# 07_-_Current_Sense.net
KiCad netlist of a schematic drawn in Altium Designer
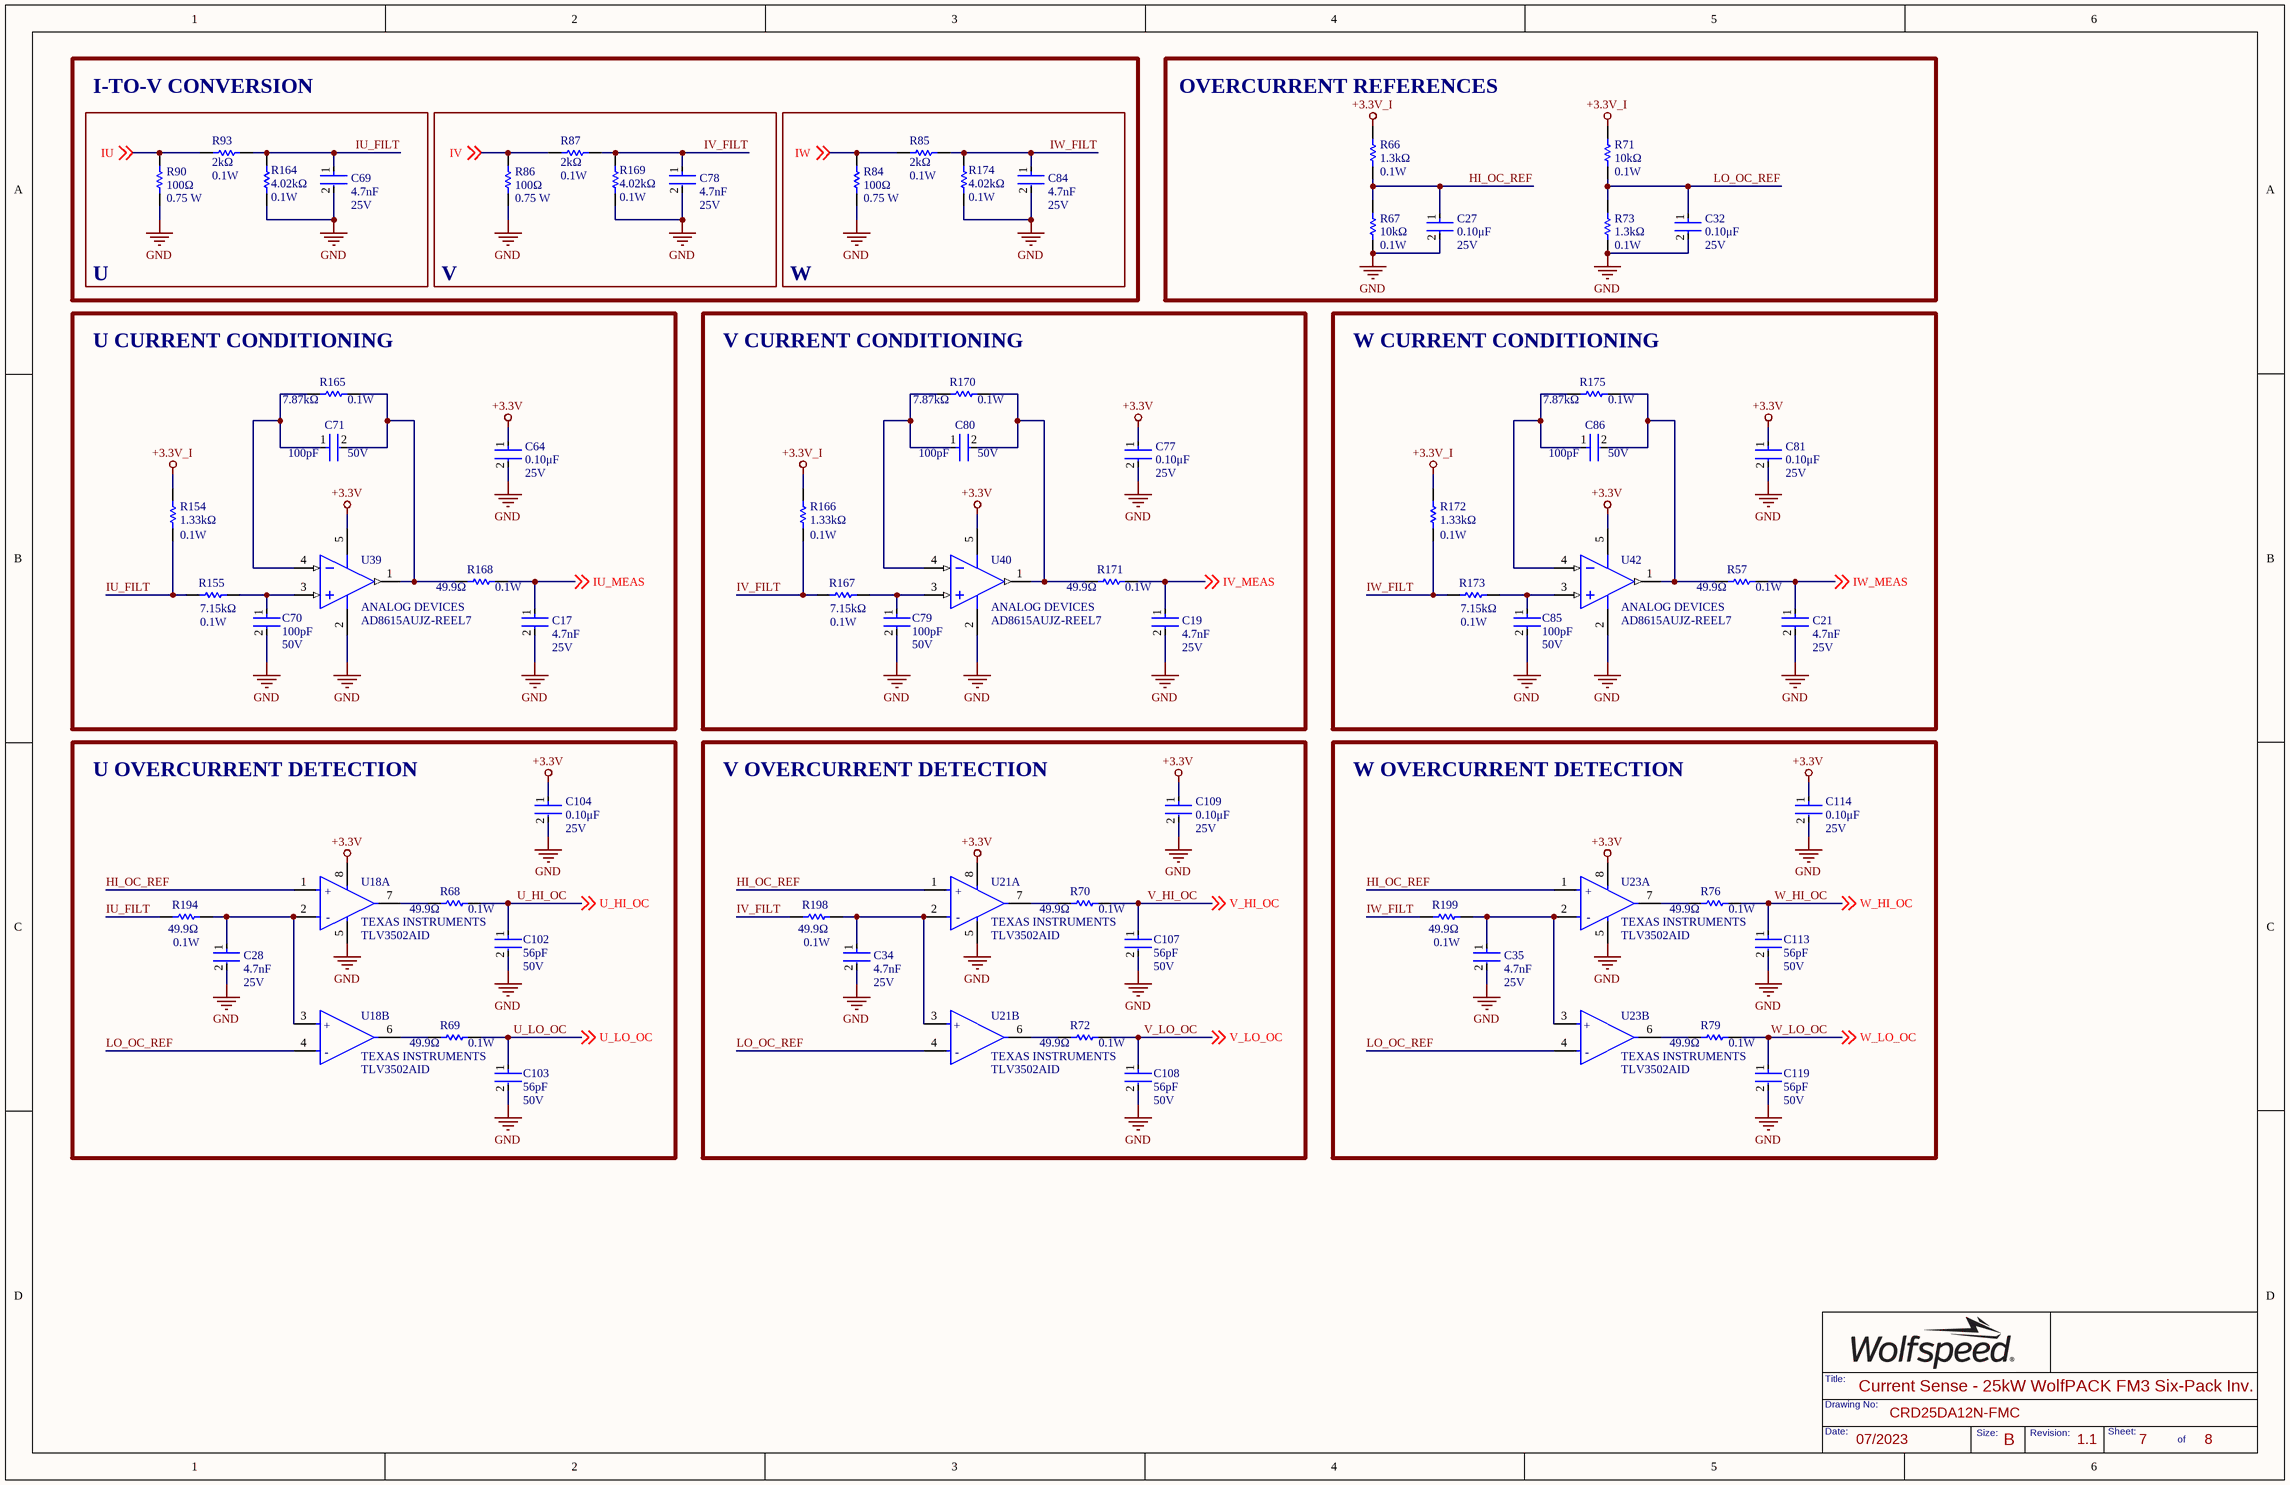
[diagram p0: 07 - Current Sense.SchDoc]

(export (version "E")
  (design (tool "Eeschema 10.0.6"))
  (components
    (comp (ref "C17")
      (value "C0603C472K3RAC7867")
      (footprint "FP-C0603C-CF-IPC_B")
      (description "CAP CER 4700PF 25V 10% X7R 0603")
      (fields
        (field (name "MANUFACTURER") "KEMET")
        (field (name "MANUFACTURER PART NUMBER") "C0603C472K3RACTU")
        (field (name "VOLTAGE RATING") "25V")
        (field (name "CAPACITANCE") "4.7nF")
      )
      (libsource (lib "Inverter_25kW") (part "C0603C472K3RAC7867"))
    )
    (comp (ref "C19")
      (value "C0603C472K3RAC7867")
      (footprint "FP-C0603C-CF-IPC_B")
      (description "CAP CER 4700PF 25V 10% X7R 0603")
      (fields
        (field (name "MANUFACTURER") "KEMET")
        (field (name "MANUFACTURER PART NUMBER") "C0603C472K3RACTU")
        (field (name "VOLTAGE RATING") "25V")
        (field (name "CAPACITANCE") "4.7nF")
      )
      (libsource (lib "Inverter_25kW") (part "C0603C472K3RAC7867"))
    )
    (comp (ref "C21")
      (value "C0603C472K3RAC7867")
      (footprint "FP-C0603C-CF-IPC_B")
      (description "CAP CER 4700PF 25V 10% X7R 0603")
      (fields
        (field (name "MANUFACTURER") "KEMET")
        (field (name "MANUFACTURER PART NUMBER") "C0603C472K3RACTU")
        (field (name "VOLTAGE RATING") "25V")
        (field (name "CAPACITANCE") "4.7nF")
      )
      (libsource (lib "Inverter_25kW") (part "C0603C472K3RAC7867"))
    )
    (comp (ref "C27")
      (value "C0603C104K3RACTU")
      (footprint "FP-C0603C-CF-IPC_B")
      (description "CAP CER 0.1UF 25V X7R 0603")
      (fields
        (field (name "VOLTAGE RATING") "25V")
        (field (name "OCTOPART") "https://octopart.com/c0603c104k3ractu-kemet-127541")
        (field (name "MANUFACTURER") "KEMET")
        (field (name "CAPACITANCE") "0.10μF")
      )
      (libsource (lib "Altium Content Vault") (part "b4654b650e69147ec39a6b967a45e02"))
    )
    (comp (ref "C28")
      (value "C0603C472K3RAC7867")
      (footprint "FP-C0603C-CF-IPC_B")
      (description "CAP CER 4700PF 25V 10% X7R 0603")
      (fields
        (field (name "MANUFACTURER") "KEMET")
        (field (name "MANUFACTURER PART NUMBER") "C0603C472K3RACTU")
        (field (name "VOLTAGE RATING") "25V")
        (field (name "CAPACITANCE") "4.7nF")
      )
      (libsource (lib "Inverter_25kW") (part "C0603C472K3RAC7867"))
    )
    (comp (ref "C32")
      (value "C0603C104K3RACTU")
      (footprint "FP-C0603C-CF-IPC_B")
      (description "CAP CER 0.1UF 25V X7R 0603")
      (fields
        (field (name "VOLTAGE RATING") "25V")
        (field (name "OCTOPART") "https://octopart.com/c0603c104k3ractu-kemet-127541")
        (field (name "MANUFACTURER") "KEMET")
        (field (name "CAPACITANCE") "0.10μF")
      )
      (libsource (lib "Altium Content Vault") (part "b4654b650e69147ec39a6b967a45e02"))
    )
    (comp (ref "C34")
      (value "C0603C472K3RAC7867")
      (footprint "FP-C0603C-CF-IPC_B")
      (description "CAP CER 4700PF 25V 10% X7R 0603")
      (fields
        (field (name "MANUFACTURER") "KEMET")
        (field (name "MANUFACTURER PART NUMBER") "C0603C472K3RACTU")
        (field (name "VOLTAGE RATING") "25V")
        (field (name "CAPACITANCE") "4.7nF")
      )
      (libsource (lib "Inverter_25kW") (part "C0603C472K3RAC7867"))
    )
    (comp (ref "C35")
      (value "C0603C472K3RAC7867")
      (footprint "FP-C0603C-CF-IPC_B")
      (description "CAP CER 4700PF 25V 10% X7R 0603")
      (fields
        (field (name "MANUFACTURER") "KEMET")
        (field (name "MANUFACTURER PART NUMBER") "C0603C472K3RACTU")
        (field (name "VOLTAGE RATING") "25V")
        (field (name "CAPACITANCE") "4.7nF")
      )
      (libsource (lib "Inverter_25kW") (part "C0603C472K3RAC7867"))
    )
    (comp (ref "C64")
      (value "C0603C104K3RACTU")
      (footprint "FP-C0603C-CF-IPC_B")
      (description "CAP CER 0.1UF 25V X7R 0603")
      (fields
        (field (name "VOLTAGE RATING") "25V")
        (field (name "OCTOPART") "https://octopart.com/c0603c104k3ractu-kemet-127541")
        (field (name "MANUFACTURER") "KEMET")
        (field (name "CAPACITANCE") "0.10μF")
      )
      (libsource (lib "Altium Content Vault") (part "b4654b650e69147ec39a6b967a45e02"))
    )
    (comp (ref "C69")
      (value "C0603C472K3RAC7867")
      (footprint "FP-C0603C-CF-IPC_B")
      (description "CAP CER 4700PF 25V 10% X7R 0603")
      (fields
        (field (name "MANUFACTURER") "KEMET")
        (field (name "MANUFACTURER PART NUMBER") "C0603C472K3RACTU")
        (field (name "VOLTAGE RATING") "25V")
        (field (name "CAPACITANCE") "4.7nF")
      )
      (libsource (lib "Inverter_25kW") (part "C0603C472K3RAC7867"))
    )
    (comp (ref "C70")
      (value "CL10C101JB8NNNC")
      (footprint "FP-C0603C-CF-IPC_B")
      (description "CAP CER 100PF 50V C0G/NP0 0603")
      (fields
        (field (name "MANUFACTURER") "SAMSUNG")
        (field (name "TOLERANCE") "5%")
        (field (name "CAPACITANCE") "100pF")
        (field (name "VOLTAGE") "50V")
      )
      (libsource (lib "Inverter_25kW") (part "CL10C101JB8NNNC"))
    )
    (comp (ref "C71")
      (value "CL10C101JB8NNNC")
      (footprint "FP-C0603C-CF-IPC_B")
      (description "CAP CER 100PF 50V C0G/NP0 0603")
      (fields
        (field (name "MANUFACTURER") "SAMSUNG")
        (field (name "TOLERANCE") "5%")
        (field (name "CAPACITANCE") "100pF")
        (field (name "VOLTAGE") "50V")
      )
      (libsource (lib "Inverter_25kW") (part "CL10C101JB8NNNC"))
    )
    (comp (ref "C77")
      (value "C0603C104K3RACTU")
      (footprint "FP-C0603C-CF-IPC_B")
      (description "CAP CER 0.1UF 25V X7R 0603")
      (fields
        (field (name "VOLTAGE RATING") "25V")
        (field (name "OCTOPART") "https://octopart.com/c0603c104k3ractu-kemet-127541")
        (field (name "MANUFACTURER") "KEMET")
        (field (name "CAPACITANCE") "0.10μF")
      )
      (libsource (lib "Altium Content Vault") (part "b4654b650e69147ec39a6b967a45e02"))
    )
    (comp (ref "C78")
      (value "C0603C472K3RAC7867")
      (footprint "FP-C0603C-CF-IPC_B")
      (description "CAP CER 4700PF 25V 10% X7R 0603")
      (fields
        (field (name "MANUFACTURER") "KEMET")
        (field (name "MANUFACTURER PART NUMBER") "C0603C472K3RACTU")
        (field (name "VOLTAGE RATING") "25V")
        (field (name "CAPACITANCE") "4.7nF")
      )
      (libsource (lib "Inverter_25kW") (part "C0603C472K3RAC7867"))
    )
    (comp (ref "C79")
      (value "CL10C101JB8NNNC")
      (footprint "FP-C0603C-CF-IPC_B")
      (description "CAP CER 100PF 50V C0G/NP0 0603")
      (fields
        (field (name "MANUFACTURER") "SAMSUNG")
        (field (name "TOLERANCE") "5%")
        (field (name "CAPACITANCE") "100pF")
        (field (name "VOLTAGE") "50V")
      )
      (libsource (lib "Inverter_25kW") (part "CL10C101JB8NNNC"))
    )
    (comp (ref "C80")
      (value "CL10C101JB8NNNC")
      (footprint "FP-C0603C-CF-IPC_B")
      (description "CAP CER 100PF 50V C0G/NP0 0603")
      (fields
        (field (name "MANUFACTURER") "SAMSUNG")
        (field (name "TOLERANCE") "5%")
        (field (name "CAPACITANCE") "100pF")
        (field (name "VOLTAGE") "50V")
      )
      (libsource (lib "Inverter_25kW") (part "CL10C101JB8NNNC"))
    )
    (comp (ref "C81")
      (value "C0603C104K3RACTU")
      (footprint "FP-C0603C-CF-IPC_B")
      (description "CAP CER 0.1UF 25V X7R 0603")
      (fields
        (field (name "VOLTAGE RATING") "25V")
        (field (name "OCTOPART") "https://octopart.com/c0603c104k3ractu-kemet-127541")
        (field (name "MANUFACTURER") "KEMET")
        (field (name "CAPACITANCE") "0.10μF")
      )
      (libsource (lib "Altium Content Vault") (part "b4654b650e69147ec39a6b967a45e02"))
    )
    (comp (ref "C84")
      (value "C0603C472K3RAC7867")
      (footprint "FP-C0603C-CF-IPC_B")
      (description "CAP CER 4700PF 25V 10% X7R 0603")
      (fields
        (field (name "MANUFACTURER") "KEMET")
        (field (name "MANUFACTURER PART NUMBER") "C0603C472K3RACTU")
        (field (name "VOLTAGE RATING") "25V")
        (field (name "CAPACITANCE") "4.7nF")
      )
      (libsource (lib "Inverter_25kW") (part "C0603C472K3RAC7867"))
    )
    (comp (ref "C85")
      (value "CL10C101JB8NNNC")
      (footprint "FP-C0603C-CF-IPC_B")
      (description "CAP CER 100PF 50V C0G/NP0 0603")
      (fields
        (field (name "MANUFACTURER") "SAMSUNG")
        (field (name "TOLERANCE") "5%")
        (field (name "CAPACITANCE") "100pF")
        (field (name "VOLTAGE") "50V")
      )
      (libsource (lib "Inverter_25kW") (part "CL10C101JB8NNNC"))
    )
    (comp (ref "C86")
      (value "CL10C101JB8NNNC")
      (footprint "FP-C0603C-CF-IPC_B")
      (description "CAP CER 100PF 50V C0G/NP0 0603")
      (fields
        (field (name "MANUFACTURER") "SAMSUNG")
        (field (name "TOLERANCE") "5%")
        (field (name "CAPACITANCE") "100pF")
        (field (name "VOLTAGE") "50V")
      )
      (libsource (lib "Inverter_25kW") (part "CL10C101JB8NNNC"))
    )
    (comp (ref "C102")
      (value "CL10C560JB8NNNC")
      (footprint "FP-C0603C-CF-IPC_B")
      (description "CAP CER 56PF 50V C0G/NP0 0603")
      (fields
        (field (name "MANUFACTURER") "SAMSUNG")
        (field (name "TOLERANCE") "5%")
        (field (name "CAPACITANCE") "56pF")
        (field (name "VOLTAGE RATING") "50V")
      )
      (libsource (lib "Inverter_25kW") (part "CL10C560JB8NNNC"))
    )
    (comp (ref "C103")
      (value "CL10C560JB8NNNC")
      (footprint "FP-C0603C-CF-IPC_B")
      (description "CAP CER 56PF 50V C0G/NP0 0603")
      (fields
        (field (name "MANUFACTURER") "SAMSUNG")
        (field (name "TOLERANCE") "5%")
        (field (name "CAPACITANCE") "56pF")
        (field (name "VOLTAGE RATING") "50V")
      )
      (libsource (lib "Inverter_25kW") (part "CL10C560JB8NNNC"))
    )
    (comp (ref "C104")
      (value "C0603C104K3RACTU")
      (footprint "FP-C0603C-CF-IPC_B")
      (description "CAP CER 0.1UF 25V X7R 0603")
      (fields
        (field (name "VOLTAGE RATING") "25V")
        (field (name "OCTOPART") "https://octopart.com/c0603c104k3ractu-kemet-127541")
        (field (name "MANUFACTURER") "KEMET")
        (field (name "CAPACITANCE") "0.10μF")
      )
      (libsource (lib "Altium Content Vault") (part "b4654b650e69147ec39a6b967a45e02"))
    )
    (comp (ref "C107")
      (value "CL10C560JB8NNNC")
      (footprint "FP-C0603C-CF-IPC_B")
      (description "CAP CER 56PF 50V C0G/NP0 0603")
      (fields
        (field (name "MANUFACTURER") "SAMSUNG")
        (field (name "TOLERANCE") "5%")
        (field (name "CAPACITANCE") "56pF")
        (field (name "VOLTAGE RATING") "50V")
      )
      (libsource (lib "Inverter_25kW") (part "CL10C560JB8NNNC"))
    )
    (comp (ref "C108")
      (value "CL10C560JB8NNNC")
      (footprint "FP-C0603C-CF-IPC_B")
      (description "CAP CER 56PF 50V C0G/NP0 0603")
      (fields
        (field (name "MANUFACTURER") "SAMSUNG")
        (field (name "TOLERANCE") "5%")
        (field (name "CAPACITANCE") "56pF")
        (field (name "VOLTAGE RATING") "50V")
      )
      (libsource (lib "Inverter_25kW") (part "CL10C560JB8NNNC"))
    )
    (comp (ref "C109")
      (value "C0603C104K3RACTU")
      (footprint "FP-C0603C-CF-IPC_B")
      (description "CAP CER 0.1UF 25V X7R 0603")
      (fields
        (field (name "VOLTAGE RATING") "25V")
        (field (name "OCTOPART") "https://octopart.com/c0603c104k3ractu-kemet-127541")
        (field (name "MANUFACTURER") "KEMET")
        (field (name "CAPACITANCE") "0.10μF")
      )
      (libsource (lib "Altium Content Vault") (part "b4654b650e69147ec39a6b967a45e02"))
    )
    (comp (ref "C113")
      (value "CL10C560JB8NNNC")
      (footprint "FP-C0603C-CF-IPC_B")
      (description "CAP CER 56PF 50V C0G/NP0 0603")
      (fields
        (field (name "MANUFACTURER") "SAMSUNG")
        (field (name "TOLERANCE") "5%")
        (field (name "CAPACITANCE") "56pF")
        (field (name "VOLTAGE RATING") "50V")
      )
      (libsource (lib "Inverter_25kW") (part "CL10C560JB8NNNC"))
    )
    (comp (ref "C114")
      (value "C0603C104K3RACTU")
      (footprint "FP-C0603C-CF-IPC_B")
      (description "CAP CER 0.1UF 25V X7R 0603")
      (fields
        (field (name "VOLTAGE RATING") "25V")
        (field (name "OCTOPART") "https://octopart.com/c0603c104k3ractu-kemet-127541")
        (field (name "MANUFACTURER") "KEMET")
        (field (name "CAPACITANCE") "0.10μF")
      )
      (libsource (lib "Altium Content Vault") (part "b4654b650e69147ec39a6b967a45e02"))
    )
    (comp (ref "C119")
      (value "CL10C560JB8NNNC")
      (footprint "FP-C0603C-CF-IPC_B")
      (description "CAP CER 56PF 50V C0G/NP0 0603")
      (fields
        (field (name "MANUFACTURER") "SAMSUNG")
        (field (name "TOLERANCE") "5%")
        (field (name "CAPACITANCE") "56pF")
        (field (name "VOLTAGE RATING") "50V")
      )
      (libsource (lib "Inverter_25kW") (part "CL10C560JB8NNNC"))
    )
    (comp (ref "R57")
      (value "ERJ-3EKF49R9V")
      (footprint "FP-MCR03-IPC_B")
      (description "RES SMD 49.9 OHM 1% 1/10W 0603")
      (fields
        (field (name "MANUFACTURER") "PANASONIC")
        (field (name "TOLERANCE") "1%")
        (field (name "RESISTANCE") "49.9Ω")
        (field (name "POWER RATING") "0.1W")
      )
      (libsource (lib "Inverter_25kW") (part "ERJ-3EKF49R9V"))
    )
    (comp (ref "R66")
      (value "ERA3AEB132V")
      (footprint "FP-MCR03-IPC_B")
      (description "RES SMD 1.3K OHM 0.1% 1/10W 0603")
      (fields
        (field (name "MANUFACTURER") "PANASONIC")
        (field (name "MANUFACTURER PART NUMBER") "ERA-3AEB132V")
        (field (name "POWER RATING") "0.1W")
        (field (name "RESISTANCE") "1.3kΩ")
      )
      (libsource (lib "Inverter_25kW") (part "ERA3AEB132V"))
    )
    (comp (ref "R67")
      (value "ERJ3EKF1002V")
      (footprint "FP-MCR03-IPC_B")
      (description "RES SMD 10K OHM 1% 1/10W 0603")
      (fields
        (field (name "MANUFACTURER") "PANASONIC")
        (field (name "MANUFACTURER PART NUMBER") "ERJ-3EKF1002V")
        (field (name "RESISTANCE") "10kΩ")
        (field (name "MAX POWER DISSIPATION") "0.1W")
      )
      (libsource (lib "Inverter_25kW") (part "ERJ3EKF1002V"))
    )
    (comp (ref "R68")
      (value "ERJ-3EKF49R9V")
      (footprint "FP-MCR03-IPC_B")
      (description "RES SMD 49.9 OHM 1% 1/10W 0603")
      (fields
        (field (name "MANUFACTURER") "PANASONIC")
        (field (name "TOLERANCE") "1%")
        (field (name "RESISTANCE") "49.9Ω")
        (field (name "POWER RATING") "0.1W")
      )
      (libsource (lib "Inverter_25kW") (part "ERJ-3EKF49R9V"))
    )
    (comp (ref "R69")
      (value "ERJ-3EKF49R9V")
      (footprint "FP-MCR03-IPC_B")
      (description "RES SMD 49.9 OHM 1% 1/10W 0603")
      (fields
        (field (name "MANUFACTURER") "PANASONIC")
        (field (name "TOLERANCE") "1%")
        (field (name "RESISTANCE") "49.9Ω")
        (field (name "POWER RATING") "0.1W")
      )
      (libsource (lib "Inverter_25kW") (part "ERJ-3EKF49R9V"))
    )
    (comp (ref "R70")
      (value "ERJ-3EKF49R9V")
      (footprint "FP-MCR03-IPC_B")
      (description "RES SMD 49.9 OHM 1% 1/10W 0603")
      (fields
        (field (name "MANUFACTURER") "PANASONIC")
        (field (name "TOLERANCE") "1%")
        (field (name "RESISTANCE") "49.9Ω")
        (field (name "POWER RATING") "0.1W")
      )
      (libsource (lib "Inverter_25kW") (part "ERJ-3EKF49R9V"))
    )
    (comp (ref "R71")
      (value "ERJ3EKF1002V")
      (footprint "FP-MCR03-IPC_B")
      (description "RES SMD 10K OHM 1% 1/10W 0603")
      (fields
        (field (name "MANUFACTURER") "PANASONIC")
        (field (name "MANUFACTURER PART NUMBER") "ERJ-3EKF1002V")
        (field (name "RESISTANCE") "10kΩ")
        (field (name "MAX POWER DISSIPATION") "0.1W")
      )
      (libsource (lib "Inverter_25kW") (part "ERJ3EKF1002V"))
    )
    (comp (ref "R72")
      (value "ERJ-3EKF49R9V")
      (footprint "FP-MCR03-IPC_B")
      (description "RES SMD 49.9 OHM 1% 1/10W 0603")
      (fields
        (field (name "MANUFACTURER") "PANASONIC")
        (field (name "TOLERANCE") "1%")
        (field (name "RESISTANCE") "49.9Ω")
        (field (name "POWER RATING") "0.1W")
      )
      (libsource (lib "Inverter_25kW") (part "ERJ-3EKF49R9V"))
    )
    (comp (ref "R73")
      (value "ERA3AEB132V")
      (footprint "FP-MCR03-IPC_B")
      (description "RES SMD 1.3K OHM 0.1% 1/10W 0603")
      (fields
        (field (name "MANUFACTURER") "PANASONIC")
        (field (name "MANUFACTURER PART NUMBER") "ERA-3AEB132V")
        (field (name "POWER RATING") "0.1W")
        (field (name "RESISTANCE") "1.3kΩ")
      )
      (libsource (lib "Inverter_25kW") (part "ERA3AEB132V"))
    )
    (comp (ref "R76")
      (value "ERJ-3EKF49R9V")
      (footprint "FP-MCR03-IPC_B")
      (description "RES SMD 49.9 OHM 1% 1/10W 0603")
      (fields
        (field (name "MANUFACTURER") "PANASONIC")
        (field (name "TOLERANCE") "1%")
        (field (name "RESISTANCE") "49.9Ω")
        (field (name "POWER RATING") "0.1W")
      )
      (libsource (lib "Inverter_25kW") (part "ERJ-3EKF49R9V"))
    )
    (comp (ref "R79")
      (value "ERJ-3EKF49R9V")
      (footprint "FP-MCR03-IPC_B")
      (description "RES SMD 49.9 OHM 1% 1/10W 0603")
      (fields
        (field (name "MANUFACTURER") "PANASONIC")
        (field (name "TOLERANCE") "1%")
        (field (name "RESISTANCE") "49.9Ω")
        (field (name "POWER RATING") "0.1W")
      )
      (libsource (lib "Inverter_25kW") (part "ERJ-3EKF49R9V"))
    )
    (comp (ref "R84")
      (value "100Ω")
      (footprint "RESC2010(5025)_N")
      (description "RES 100 OHM 1% 3/4W 2010")
      (fields
        (field (name "TOLERANCE") "1 %")
        (field (name "POWER") "0.75 W")
        (field (name "MANUFACTURER") "YAGEO")
      )
      (libsource (lib "Altium Content Vault") (part "RES"))
    )
    (comp (ref "R85")
      (value "RT0603DRE072KL")
      (footprint "FP-MCR03-IPC_B")
      (description "RES SMD 2K OHM 0.5% 1/10W 0603")
      (fields
        (field (name "MANUFACTURER") "YAGEO")
        (field (name "TOLERANCE") "0.5%")
        (field (name "RESISTANCE") "2kΩ")
        (field (name "POWER RATING") "0.1W")
      )
      (libsource (lib "Inverter_25kW") (part "RT0603DRE072KL"))
    )
    (comp (ref "R86")
      (value "100Ω")
      (footprint "RESC2010(5025)_N")
      (description "RES 100 OHM 1% 3/4W 2010")
      (fields
        (field (name "TOLERANCE") "1 %")
        (field (name "POWER") "0.75 W")
        (field (name "MANUFACTURER") "YAGEO")
      )
      (libsource (lib "Altium Content Vault") (part "RES"))
    )
    (comp (ref "R87")
      (value "RT0603DRE072KL")
      (footprint "FP-MCR03-IPC_B")
      (description "RES SMD 2K OHM 0.5% 1/10W 0603")
      (fields
        (field (name "MANUFACTURER") "YAGEO")
        (field (name "TOLERANCE") "0.5%")
        (field (name "RESISTANCE") "2kΩ")
        (field (name "POWER RATING") "0.1W")
      )
      (libsource (lib "Inverter_25kW") (part "RT0603DRE072KL"))
    )
    (comp (ref "R90")
      (value "100Ω")
      (footprint "RESC2010(5025)_N")
      (description "RES 100 OHM 1% 3/4W 2010")
      (fields
        (field (name "TOLERANCE") "1 %")
        (field (name "POWER") "0.75 W")
        (field (name "MANUFACTURER") "YAGEO")
      )
      (libsource (lib "Altium Content Vault") (part "RES"))
    )
    (comp (ref "R93")
      (value "RT0603DRE072KL")
      (footprint "FP-MCR03-IPC_B")
      (description "RES SMD 2K OHM 0.5% 1/10W 0603")
      (fields
        (field (name "MANUFACTURER") "YAGEO")
        (field (name "TOLERANCE") "0.5%")
        (field (name "RESISTANCE") "2kΩ")
        (field (name "POWER RATING") "0.1W")
      )
      (libsource (lib "Inverter_25kW") (part "RT0603DRE072KL"))
    )
    (comp (ref "R154")
      (value "RMCF0603FT1K33")
      (footprint "FP-MCR03-IPC_B")
      (description "RES 1.33K OHM 1% 1/10W 0603")
      (fields
        (field (name "MANUFACTURER") "STACKPOLE")
        (field (name "TOLERANCE") "1%")
        (field (name "POWER RATING") "0.1W")
        (field (name "RESISTANCE") "1.33kΩ")
      )
      (libsource (lib "Inverter_25kW") (part "RMCF0603FT1K33"))
    )
    (comp (ref "R155")
      (value "RMCF0603FT7K15")
      (footprint "FP-MCR03-IPC_B")
      (description "RES 7.15K OHM 1% 1/10W 0603")
      (fields
        (field (name "MANUFACTURER") "STACKPOLE")
        (field (name "TOLERANCE") "1%")
        (field (name "RESISTANCE") "7.15kΩ")
        (field (name "POWER RATING") "0.1W")
      )
      (libsource (lib "Inverter_25kW") (part "RMCF0603FT7K15"))
    )
    (comp (ref "R164")
      (value "ERA3AEB4021V")
      (footprint "FP-MCR03-IPC_B")
      (description "RES SMD 4.02KOHM 0.1% 1/10W 0603")
      (fields
        (field (name "MANUFACTURER") "PANASONIC")
        (field (name "MANUFACTURER PART NUMBER") "ERA-3AEB4021V")
        (field (name "RESISTANCE") "4.02kΩ")
        (field (name "POWER RATING") "0.1W")
      )
      (libsource (lib "Inverter_25kW") (part "ERA3AEB4021V"))
    )
    (comp (ref "R165")
      (value "RC0603FR-077K87L")
      (footprint "FP-MCR03-IPC_B")
      (description "RES 7.87K OHM 1% 1/10W 0603")
      (fields
        (field (name "MANUFACTURER") "YAGEO")
        (field (name "TOLERANCE") "1%")
        (field (name "RESISTANCE") "7.87kΩ")
        (field (name "MAX POWER DISSIPATION") "0.1W")
      )
      (libsource (lib "Inverter_25kW") (part "RC0603FR-077K87L"))
    )
    (comp (ref "R166")
      (value "RMCF0603FT1K33")
      (footprint "FP-MCR03-IPC_B")
      (description "RES 1.33K OHM 1% 1/10W 0603")
      (fields
        (field (name "MANUFACTURER") "STACKPOLE")
        (field (name "TOLERANCE") "1%")
        (field (name "POWER RATING") "0.1W")
        (field (name "RESISTANCE") "1.33kΩ")
      )
      (libsource (lib "Inverter_25kW") (part "RMCF0603FT1K33"))
    )
    (comp (ref "R167")
      (value "RMCF0603FT7K15")
      (footprint "FP-MCR03-IPC_B")
      (description "RES 7.15K OHM 1% 1/10W 0603")
      (fields
        (field (name "MANUFACTURER") "STACKPOLE")
        (field (name "TOLERANCE") "1%")
        (field (name "RESISTANCE") "7.15kΩ")
        (field (name "POWER RATING") "0.1W")
      )
      (libsource (lib "Inverter_25kW") (part "RMCF0603FT7K15"))
    )
    (comp (ref "R168")
      (value "ERJ-3EKF49R9V")
      (footprint "FP-MCR03-IPC_B")
      (description "RES SMD 49.9 OHM 1% 1/10W 0603")
      (fields
        (field (name "MANUFACTURER") "PANASONIC")
        (field (name "TOLERANCE") "1%")
        (field (name "RESISTANCE") "49.9Ω")
        (field (name "POWER RATING") "0.1W")
      )
      (libsource (lib "Inverter_25kW") (part "ERJ-3EKF49R9V"))
    )
    (comp (ref "R169")
      (value "ERA3AEB4021V")
      (footprint "FP-MCR03-IPC_B")
      (description "RES SMD 4.02KOHM 0.1% 1/10W 0603")
      (fields
        (field (name "MANUFACTURER") "PANASONIC")
        (field (name "MANUFACTURER PART NUMBER") "ERA-3AEB4021V")
        (field (name "RESISTANCE") "4.02kΩ")
        (field (name "POWER RATING") "0.1W")
      )
      (libsource (lib "Inverter_25kW") (part "ERA3AEB4021V"))
    )
    (comp (ref "R170")
      (value "RC0603FR-077K87L")
      (footprint "FP-MCR03-IPC_B")
      (description "RES 7.87K OHM 1% 1/10W 0603")
      (fields
        (field (name "MANUFACTURER") "YAGEO")
        (field (name "TOLERANCE") "1%")
        (field (name "RESISTANCE") "7.87kΩ")
        (field (name "MAX POWER DISSIPATION") "0.1W")
      )
      (libsource (lib "Inverter_25kW") (part "RC0603FR-077K87L"))
    )
    (comp (ref "R171")
      (value "ERJ-3EKF49R9V")
      (footprint "FP-MCR03-IPC_B")
      (description "RES SMD 49.9 OHM 1% 1/10W 0603")
      (fields
        (field (name "MANUFACTURER") "PANASONIC")
        (field (name "TOLERANCE") "1%")
        (field (name "RESISTANCE") "49.9Ω")
        (field (name "POWER RATING") "0.1W")
      )
      (libsource (lib "Inverter_25kW") (part "ERJ-3EKF49R9V"))
    )
    (comp (ref "R172")
      (value "RMCF0603FT1K33")
      (footprint "FP-MCR03-IPC_B")
      (description "RES 1.33K OHM 1% 1/10W 0603")
      (fields
        (field (name "MANUFACTURER") "STACKPOLE")
        (field (name "TOLERANCE") "1%")
        (field (name "POWER RATING") "0.1W")
        (field (name "RESISTANCE") "1.33kΩ")
      )
      (libsource (lib "Inverter_25kW") (part "RMCF0603FT1K33"))
    )
    (comp (ref "R173")
      (value "RMCF0603FT7K15")
      (footprint "FP-MCR03-IPC_B")
      (description "RES 7.15K OHM 1% 1/10W 0603")
      (fields
        (field (name "MANUFACTURER") "STACKPOLE")
        (field (name "TOLERANCE") "1%")
        (field (name "RESISTANCE") "7.15kΩ")
        (field (name "POWER RATING") "0.1W")
      )
      (libsource (lib "Inverter_25kW") (part "RMCF0603FT7K15"))
    )
    (comp (ref "R174")
      (value "ERA3AEB4021V")
      (footprint "FP-MCR03-IPC_B")
      (description "RES SMD 4.02KOHM 0.1% 1/10W 0603")
      (fields
        (field (name "MANUFACTURER") "PANASONIC")
        (field (name "MANUFACTURER PART NUMBER") "ERA-3AEB4021V")
        (field (name "RESISTANCE") "4.02kΩ")
        (field (name "POWER RATING") "0.1W")
      )
      (libsource (lib "Inverter_25kW") (part "ERA3AEB4021V"))
    )
    (comp (ref "R175")
      (value "RC0603FR-077K87L")
      (footprint "FP-MCR03-IPC_B")
      (description "RES 7.87K OHM 1% 1/10W 0603")
      (fields
        (field (name "MANUFACTURER") "YAGEO")
        (field (name "TOLERANCE") "1%")
        (field (name "RESISTANCE") "7.87kΩ")
        (field (name "MAX POWER DISSIPATION") "0.1W")
      )
      (libsource (lib "Inverter_25kW") (part "RC0603FR-077K87L"))
    )
    (comp (ref "R194")
      (value "ERJ-3EKF49R9V")
      (footprint "FP-MCR03-IPC_B")
      (description "RES SMD 49.9 OHM 1% 1/10W 0603")
      (fields
        (field (name "MANUFACTURER") "PANASONIC")
        (field (name "TOLERANCE") "1%")
        (field (name "RESISTANCE") "49.9Ω")
        (field (name "POWER RATING") "0.1W")
      )
      (libsource (lib "Inverter_25kW") (part "ERJ-3EKF49R9V"))
    )
    (comp (ref "R198")
      (value "ERJ-3EKF49R9V")
      (footprint "FP-MCR03-IPC_B")
      (description "RES SMD 49.9 OHM 1% 1/10W 0603")
      (fields
        (field (name "MANUFACTURER") "PANASONIC")
        (field (name "TOLERANCE") "1%")
        (field (name "RESISTANCE") "49.9Ω")
        (field (name "POWER RATING") "0.1W")
      )
      (libsource (lib "Inverter_25kW") (part "ERJ-3EKF49R9V"))
    )
    (comp (ref "R199")
      (value "ERJ-3EKF49R9V")
      (footprint "FP-MCR03-IPC_B")
      (description "RES SMD 49.9 OHM 1% 1/10W 0603")
      (fields
        (field (name "MANUFACTURER") "PANASONIC")
        (field (name "TOLERANCE") "1%")
        (field (name "RESISTANCE") "49.9Ω")
        (field (name "POWER RATING") "0.1W")
      )
      (libsource (lib "Inverter_25kW") (part "ERJ-3EKF49R9V"))
    )
    (comp (ref "U18")
      (value "TLV3502AID")
      (footprint "FP-D0008A-IPC_B")
      (description "IC COMPARATOR R-R HI-SPD 8-SOIC")
      (fields
        (field (name "OCTOPART") "https://octopart.com/tlv3502aid-texas+instruments-428400")
        (field (name "MANUFACTURER") "TEXAS INSTRUMENTS")
        (field (name "MANUFACTURER PRINT") "TEXAS INSTRUMENTS")
      )
      (libsource (lib "Inverter_25kW") (part "CMP-04896-000023-1"))
    )
    (comp (ref "U21")
      (value "TLV3502AID")
      (footprint "FP-D0008A-IPC_B")
      (description "IC COMPARATOR R-R HI-SPD 8-SOIC")
      (fields
        (field (name "OCTOPART") "https://octopart.com/tlv3502aid-texas+instruments-428400")
        (field (name "MANUFACTURER") "TEXAS INSTRUMENTS")
        (field (name "MANUFACTURER PRINT") "TEXAS INSTRUMENTS")
      )
      (libsource (lib "Inverter_25kW") (part "CMP-04896-000023-1"))
    )
    (comp (ref "U23")
      (value "TLV3502AID")
      (footprint "FP-D0008A-IPC_B")
      (description "IC COMPARATOR R-R HI-SPD 8-SOIC")
      (fields
        (field (name "OCTOPART") "https://octopart.com/tlv3502aid-texas+instruments-428400")
        (field (name "MANUFACTURER") "TEXAS INSTRUMENTS")
        (field (name "MANUFACTURER PRINT") "TEXAS INSTRUMENTS")
      )
      (libsource (lib "Inverter_25kW") (part "CMP-04896-000023-1"))
    )
    (comp (ref "U39")
      (value "AD8615AUJZ-REEL7")
      (footprint "ADI-UJ-5_M")
      (description "IC OPAMP GP 1 CIRCUIT TSOT23-5")
      (fields
        (field (name "MANUFACTURER") "ANALOG DEVICES")
        (field (name "GENERIC PART NUMBER") "AD8615")
        (field (name "MANUFACTURER PART NUMBER") "AD8615AUJZ-REEL7")
      )
      (libsource (lib "Altium Content Vault") (part "ADI-ADxxxx-X-5"))
    )
    (comp (ref "U40")
      (value "AD8615AUJZ-REEL7")
      (footprint "ADI-UJ-5_M")
      (description "IC OPAMP GP 1 CIRCUIT TSOT23-5")
      (fields
        (field (name "MANUFACTURER") "ANALOG DEVICES")
        (field (name "GENERIC PART NUMBER") "AD8615")
        (field (name "MANUFACTURER PART NUMBER") "AD8615AUJZ-REEL7")
      )
      (libsource (lib "Altium Content Vault") (part "ADI-ADxxxx-X-5"))
    )
    (comp (ref "U42")
      (value "AD8615AUJZ-REEL7")
      (footprint "ADI-UJ-5_M")
      (description "IC OPAMP GP 1 CIRCUIT TSOT23-5")
      (fields
        (field (name "MANUFACTURER") "ANALOG DEVICES")
        (field (name "GENERIC PART NUMBER") "AD8615")
        (field (name "MANUFACTURER PART NUMBER") "AD8615AUJZ-REEL7")
      )
      (libsource (lib "Altium Content Vault") (part "ADI-ADxxxx-X-5"))
    )
  )
  (nets
    (net (code "1") (name "+3.3V") (class "Default")
      (node (ref "C104") (pin "1") (pinfunction "1_1") (pintype "passive"))
      (node (ref "C109") (pin "1") (pinfunction "1_1") (pintype "passive"))
      (node (ref "C114") (pin "1") (pinfunction "1_1") (pintype "passive"))
      (node (ref "C64") (pin "1") (pinfunction "1_1") (pintype "passive"))
      (node (ref "C77") (pin "1") (pinfunction "1_1") (pintype "passive"))
      (node (ref "C81") (pin "1") (pinfunction "1_1") (pintype "passive"))
      (node (ref "U18") (pin "8") (pinfunction "V+_8") (pintype "power_in"))
      (node (ref "U21") (pin "8") (pinfunction "V+_8") (pintype "power_in"))
      (node (ref "U23") (pin "8") (pinfunction "V+_8") (pintype "power_in"))
      (node (ref "U39") (pin "5") (pinfunction "+V_5") (pintype "power_in"))
      (node (ref "U40") (pin "5") (pinfunction "+V_5") (pintype "power_in"))
      (node (ref "U42") (pin "5") (pinfunction "+V_5") (pintype "power_in"))
    )
    (net (code "2") (name "+3.3V_I") (class "Default")
      (node (ref "R154") (pin "2") (pinfunction "2_2") (pintype "passive"))
      (node (ref "R166") (pin "2") (pinfunction "2_2") (pintype "passive"))
      (node (ref "R172") (pin "2") (pinfunction "2_2") (pintype "passive"))
      (node (ref "R66") (pin "2") (pinfunction "2_2") (pintype "passive"))
      (node (ref "R71") (pin "2") (pinfunction "2_2") (pintype "passive"))
    )
    (net (code "3") (name "/HI_OC_REF") (class "Default")
      (node (ref "C27") (pin "1") (pinfunction "1_1") (pintype "passive"))
      (node (ref "R66") (pin "1") (pinfunction "1_1") (pintype "passive"))
      (node (ref "R67") (pin "2") (pinfunction "2_2") (pintype "passive"))
      (node (ref "U18") (pin "1") (pinfunction "+IN_A_1") (pintype "tri_state"))
      (node (ref "U21") (pin "1") (pinfunction "+IN_A_1") (pintype "tri_state"))
      (node (ref "U23") (pin "1") (pinfunction "+IN_A_1") (pintype "tri_state"))
    )
    (net (code "4") (name "/IU_FILT") (class "Default")
      (node (ref "C69") (pin "1") (pinfunction "1_1") (pintype "passive"))
      (node (ref "R154") (pin "1") (pinfunction "1_1") (pintype "passive"))
      (node (ref "R155") (pin "1") (pinfunction "1_1") (pintype "passive"))
      (node (ref "R164") (pin "2") (pinfunction "2_2") (pintype "passive"))
      (node (ref "R194") (pin "1") (pinfunction "1_1") (pintype "passive"))
      (node (ref "R93") (pin "2") (pinfunction "2_2") (pintype "passive"))
    )
    (net (code "5") (name "/IV_FILT") (class "Default")
      (node (ref "C78") (pin "1") (pinfunction "1_1") (pintype "passive"))
      (node (ref "R166") (pin "1") (pinfunction "1_1") (pintype "passive"))
      (node (ref "R167") (pin "1") (pinfunction "1_1") (pintype "passive"))
      (node (ref "R169") (pin "2") (pinfunction "2_2") (pintype "passive"))
      (node (ref "R198") (pin "1") (pinfunction "1_1") (pintype "passive"))
      (node (ref "R87") (pin "2") (pinfunction "2_2") (pintype "passive"))
    )
    (net (code "6") (name "/IW_FILT") (class "Default")
      (node (ref "C84") (pin "1") (pinfunction "1_1") (pintype "passive"))
      (node (ref "R172") (pin "1") (pinfunction "1_1") (pintype "passive"))
      (node (ref "R173") (pin "1") (pinfunction "1_1") (pintype "passive"))
      (node (ref "R174") (pin "2") (pinfunction "2_2") (pintype "passive"))
      (node (ref "R199") (pin "1") (pinfunction "1_1") (pintype "passive"))
      (node (ref "R85") (pin "2") (pinfunction "2_2") (pintype "passive"))
    )
    (net (code "7") (name "/LO_OC_REF") (class "Default")
      (node (ref "C32") (pin "1") (pinfunction "1_1") (pintype "passive"))
      (node (ref "R71") (pin "1") (pinfunction "1_1") (pintype "passive"))
      (node (ref "R73") (pin "2") (pinfunction "2_2") (pintype "passive"))
      (node (ref "U18") (pin "4") (pinfunction "-IN_B_4") (pintype "tri_state"))
      (node (ref "U21") (pin "4") (pinfunction "-IN_B_4") (pintype "tri_state"))
      (node (ref "U23") (pin "4") (pinfunction "-IN_B_4") (pintype "tri_state"))
    )
    (net (code "8") (name "GND") (class "Default")
      (node (ref "C102") (pin "2") (pinfunction "2_2") (pintype "passive"))
      (node (ref "C103") (pin "2") (pinfunction "2_2") (pintype "passive"))
      (node (ref "C104") (pin "2") (pinfunction "2_2") (pintype "passive"))
      (node (ref "C107") (pin "2") (pinfunction "2_2") (pintype "passive"))
      (node (ref "C108") (pin "2") (pinfunction "2_2") (pintype "passive"))
      (node (ref "C109") (pin "2") (pinfunction "2_2") (pintype "passive"))
      (node (ref "C113") (pin "2") (pinfunction "2_2") (pintype "passive"))
      (node (ref "C114") (pin "2") (pinfunction "2_2") (pintype "passive"))
      (node (ref "C119") (pin "2") (pinfunction "2_2") (pintype "passive"))
      (node (ref "C17") (pin "2") (pinfunction "2_2") (pintype "passive"))
      (node (ref "C19") (pin "2") (pinfunction "2_2") (pintype "passive"))
      (node (ref "C21") (pin "2") (pinfunction "2_2") (pintype "passive"))
      (node (ref "C27") (pin "2") (pinfunction "2_2") (pintype "passive"))
      (node (ref "C28") (pin "2") (pinfunction "2_2") (pintype "passive"))
      (node (ref "C32") (pin "2") (pinfunction "2_2") (pintype "passive"))
      (node (ref "C34") (pin "2") (pinfunction "2_2") (pintype "passive"))
      (node (ref "C35") (pin "2") (pinfunction "2_2") (pintype "passive"))
      (node (ref "C64") (pin "2") (pinfunction "2_2") (pintype "passive"))
      (node (ref "C69") (pin "2") (pinfunction "2_2") (pintype "passive"))
      (node (ref "C70") (pin "2") (pinfunction "2_2") (pintype "passive"))
      (node (ref "C77") (pin "2") (pinfunction "2_2") (pintype "passive"))
      (node (ref "C78") (pin "2") (pinfunction "2_2") (pintype "passive"))
      (node (ref "C79") (pin "2") (pinfunction "2_2") (pintype "passive"))
      (node (ref "C81") (pin "2") (pinfunction "2_2") (pintype "passive"))
      (node (ref "C84") (pin "2") (pinfunction "2_2") (pintype "passive"))
      (node (ref "C85") (pin "2") (pinfunction "2_2") (pintype "passive"))
      (node (ref "R164") (pin "1") (pinfunction "1_1") (pintype "passive"))
      (node (ref "R169") (pin "1") (pinfunction "1_1") (pintype "passive"))
      (node (ref "R174") (pin "1") (pinfunction "1_1") (pintype "passive"))
      (node (ref "R67") (pin "1") (pinfunction "1_1") (pintype "passive"))
      (node (ref "R73") (pin "1") (pinfunction "1_1") (pintype "passive"))
      (node (ref "R84") (pin "1") (pinfunction "1_1") (pintype "passive"))
      (node (ref "R86") (pin "1") (pinfunction "1_1") (pintype "passive"))
      (node (ref "R90") (pin "1") (pinfunction "1_1") (pintype "passive"))
      (node (ref "U18") (pin "5") (pinfunction "V-_5") (pintype "power_in"))
      (node (ref "U21") (pin "5") (pinfunction "V-_5") (pintype "power_in"))
      (node (ref "U23") (pin "5") (pinfunction "V-_5") (pintype "power_in"))
      (node (ref "U39") (pin "2") (pinfunction "-V_2") (pintype "power_in"))
      (node (ref "U40") (pin "2") (pinfunction "-V_2") (pintype "power_in"))
      (node (ref "U42") (pin "2") (pinfunction "-V_2") (pintype "power_in"))
    )
    (net (code "9") (name "IU") (class "Default")
      (node (ref "R90") (pin "2") (pinfunction "2_2") (pintype "passive"))
      (node (ref "R93") (pin "1") (pinfunction "1_1") (pintype "passive"))
    )
    (net (code "10") (name "IU_MEAS") (class "Default")
      (node (ref "C17") (pin "1") (pinfunction "1_1") (pintype "passive"))
      (node (ref "R168") (pin "2") (pinfunction "2_2") (pintype "passive"))
    )
    (net (code "11") (name "IV") (class "Default")
      (node (ref "R86") (pin "2") (pinfunction "2_2") (pintype "passive"))
      (node (ref "R87") (pin "1") (pinfunction "1_1") (pintype "passive"))
    )
    (net (code "12") (name "IV_MEAS") (class "Default")
      (node (ref "C19") (pin "1") (pinfunction "1_1") (pintype "passive"))
      (node (ref "R171") (pin "2") (pinfunction "2_2") (pintype "passive"))
    )
    (net (code "13") (name "IW") (class "Default")
      (node (ref "R84") (pin "2") (pinfunction "2_2") (pintype "passive"))
      (node (ref "R85") (pin "1") (pinfunction "1_1") (pintype "passive"))
    )
    (net (code "14") (name "IW_MEAS") (class "Default")
      (node (ref "C21") (pin "1") (pinfunction "1_1") (pintype "passive"))
      (node (ref "R57") (pin "2") (pinfunction "2_2") (pintype "passive"))
    )
    (net (code "15") (name "Net-(U18A--IN_A)") (class "Default")
      (node (ref "C28") (pin "1") (pinfunction "1_1") (pintype "passive"))
      (node (ref "R194") (pin "2") (pinfunction "2_2") (pintype "passive"))
      (node (ref "U18") (pin "2") (pinfunction "-IN_A_2") (pintype "tri_state"))
      (node (ref "U18") (pin "3") (pinfunction "+IN_B_3") (pintype "tri_state"))
    )
    (net (code "16") (name "Net-(U18A-OUT_A)") (class "Default")
      (node (ref "R68") (pin "1") (pinfunction "1_1") (pintype "passive"))
      (node (ref "U18") (pin "7") (pinfunction "OUT_A_7") (pintype "passive"))
    )
    (net (code "17") (name "Net-(U18B-OUT_B)") (class "Default")
      (node (ref "R69") (pin "1") (pinfunction "1_1") (pintype "passive"))
      (node (ref "U18") (pin "6") (pinfunction "OUT_B_6") (pintype "passive"))
    )
    (net (code "18") (name "Net-(U21A--IN_A)") (class "Default")
      (node (ref "C34") (pin "1") (pinfunction "1_1") (pintype "passive"))
      (node (ref "R198") (pin "2") (pinfunction "2_2") (pintype "passive"))
      (node (ref "U21") (pin "2") (pinfunction "-IN_A_2") (pintype "tri_state"))
      (node (ref "U21") (pin "3") (pinfunction "+IN_B_3") (pintype "tri_state"))
    )
    (net (code "19") (name "Net-(U21A-OUT_A)") (class "Default")
      (node (ref "R70") (pin "1") (pinfunction "1_1") (pintype "passive"))
      (node (ref "U21") (pin "7") (pinfunction "OUT_A_7") (pintype "passive"))
    )
    (net (code "20") (name "Net-(U21B-OUT_B)") (class "Default")
      (node (ref "R72") (pin "1") (pinfunction "1_1") (pintype "passive"))
      (node (ref "U21") (pin "6") (pinfunction "OUT_B_6") (pintype "passive"))
    )
    (net (code "21") (name "Net-(U23A--IN_A)") (class "Default")
      (node (ref "C35") (pin "1") (pinfunction "1_1") (pintype "passive"))
      (node (ref "R199") (pin "2") (pinfunction "2_2") (pintype "passive"))
      (node (ref "U23") (pin "2") (pinfunction "-IN_A_2") (pintype "tri_state"))
      (node (ref "U23") (pin "3") (pinfunction "+IN_B_3") (pintype "tri_state"))
    )
    (net (code "22") (name "Net-(U23A-OUT_A)") (class "Default")
      (node (ref "R76") (pin "1") (pinfunction "1_1") (pintype "passive"))
      (node (ref "U23") (pin "7") (pinfunction "OUT_A_7") (pintype "passive"))
    )
    (net (code "23") (name "Net-(U23B-OUT_B)") (class "Default")
      (node (ref "R79") (pin "1") (pinfunction "1_1") (pintype "passive"))
      (node (ref "U23") (pin "6") (pinfunction "OUT_B_6") (pintype "passive"))
    )
    (net (code "24") (name "Net-(U39-+IN)") (class "Default")
      (node (ref "C70") (pin "1") (pinfunction "1_1") (pintype "passive"))
      (node (ref "R155") (pin "2") (pinfunction "2_2") (pintype "passive"))
      (node (ref "U39") (pin "3") (pinfunction "+IN_3") (pintype "input"))
    )
    (net (code "25") (name "Net-(U39--IN)") (class "Default")
      (node (ref "C71") (pin "1") (pinfunction "1_1") (pintype "passive"))
      (node (ref "R165") (pin "1") (pinfunction "1_1") (pintype "passive"))
      (node (ref "U39") (pin "4") (pinfunction "-IN_4") (pintype "input"))
    )
    (net (code "26") (name "Net-(U39-OUT)") (class "Default")
      (node (ref "C71") (pin "2") (pinfunction "2_2") (pintype "passive"))
      (node (ref "R165") (pin "2") (pinfunction "2_2") (pintype "passive"))
      (node (ref "R168") (pin "1") (pinfunction "1_1") (pintype "passive"))
      (node (ref "U39") (pin "1") (pinfunction "OUT_1") (pintype "output"))
    )
    (net (code "27") (name "Net-(U40-+IN)") (class "Default")
      (node (ref "C79") (pin "1") (pinfunction "1_1") (pintype "passive"))
      (node (ref "R167") (pin "2") (pinfunction "2_2") (pintype "passive"))
      (node (ref "U40") (pin "3") (pinfunction "+IN_3") (pintype "input"))
    )
    (net (code "28") (name "Net-(U40--IN)") (class "Default")
      (node (ref "C80") (pin "1") (pinfunction "1_1") (pintype "passive"))
      (node (ref "R170") (pin "1") (pinfunction "1_1") (pintype "passive"))
      (node (ref "U40") (pin "4") (pinfunction "-IN_4") (pintype "input"))
    )
    (net (code "29") (name "Net-(U40-OUT)") (class "Default")
      (node (ref "C80") (pin "2") (pinfunction "2_2") (pintype "passive"))
      (node (ref "R170") (pin "2") (pinfunction "2_2") (pintype "passive"))
      (node (ref "R171") (pin "1") (pinfunction "1_1") (pintype "passive"))
      (node (ref "U40") (pin "1") (pinfunction "OUT_1") (pintype "output"))
    )
    (net (code "30") (name "Net-(U42-+IN)") (class "Default")
      (node (ref "C85") (pin "1") (pinfunction "1_1") (pintype "passive"))
      (node (ref "R173") (pin "2") (pinfunction "2_2") (pintype "passive"))
      (node (ref "U42") (pin "3") (pinfunction "+IN_3") (pintype "input"))
    )
    (net (code "31") (name "Net-(U42--IN)") (class "Default")
      (node (ref "C86") (pin "1") (pinfunction "1_1") (pintype "passive"))
      (node (ref "R175") (pin "1") (pinfunction "1_1") (pintype "passive"))
      (node (ref "U42") (pin "4") (pinfunction "-IN_4") (pintype "input"))
    )
    (net (code "32") (name "Net-(U42-OUT)") (class "Default")
      (node (ref "C86") (pin "2") (pinfunction "2_2") (pintype "passive"))
      (node (ref "R175") (pin "2") (pinfunction "2_2") (pintype "passive"))
      (node (ref "R57") (pin "1") (pinfunction "1_1") (pintype "passive"))
      (node (ref "U42") (pin "1") (pinfunction "OUT_1") (pintype "output"))
    )
    (net (code "33") (name "U_HI_OC") (class "Default")
      (node (ref "C102") (pin "1") (pinfunction "1_1") (pintype "passive"))
      (node (ref "R68") (pin "2") (pinfunction "2_2") (pintype "passive"))
    )
    (net (code "34") (name "U_LO_OC") (class "Default")
      (node (ref "C103") (pin "1") (pinfunction "1_1") (pintype "passive"))
      (node (ref "R69") (pin "2") (pinfunction "2_2") (pintype "passive"))
    )
    (net (code "35") (name "V_HI_OC") (class "Default")
      (node (ref "C107") (pin "1") (pinfunction "1_1") (pintype "passive"))
      (node (ref "R70") (pin "2") (pinfunction "2_2") (pintype "passive"))
    )
    (net (code "36") (name "V_LO_OC") (class "Default")
      (node (ref "C108") (pin "1") (pinfunction "1_1") (pintype "passive"))
      (node (ref "R72") (pin "2") (pinfunction "2_2") (pintype "passive"))
    )
    (net (code "37") (name "W_HI_OC") (class "Default")
      (node (ref "C113") (pin "1") (pinfunction "1_1") (pintype "passive"))
      (node (ref "R76") (pin "2") (pinfunction "2_2") (pintype "passive"))
    )
    (net (code "38") (name "W_LO_OC") (class "Default")
      (node (ref "C119") (pin "1") (pinfunction "1_1") (pintype "passive"))
      (node (ref "R79") (pin "2") (pinfunction "2_2") (pintype "passive"))
    )
  )
)
